# Power.net
KiCad netlist of a schematic drawn in Altium Designer
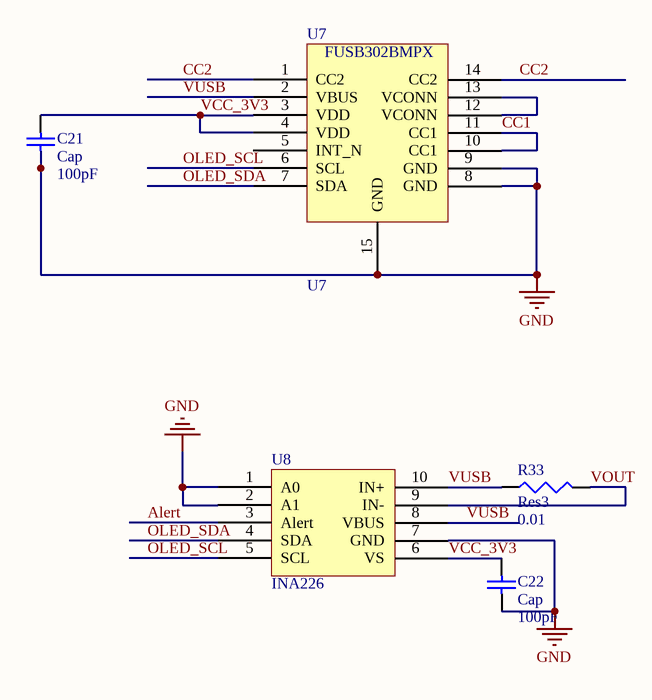
[diagram p0: Power.SchDoc]

(export (version "E")
  (design (tool "Eeschema 10.0.6"))
  (components
    (comp (ref "C21")
      (value "Cap")
      (footprint "0402")
      (description "Capacitor")
      (fields (field (name "ALTIUM_VALUE") "100pF") (field (name "PUBLISHER") "Altium Limited"))
      (libsource (lib "Miscellaneous Devices") (part "Cap"))
    )
    (comp (ref "C22")
      (value "Cap")
      (footprint "0402")
      (description "Capacitor")
      (fields (field (name "ALTIUM_VALUE") "100pF") (field (name "PUBLISHER") "Altium Limited"))
      (libsource (lib "Miscellaneous Devices") (part "Cap"))
    )
    (comp (ref "R33")
      (value "Res3")
      (footprint "C2512")
      (description "Resistor")
      (fields (field (name "ALTIUM_VALUE") "0.01") (field (name "PUBLISHER") "Altium Limited"))
      (libsource (lib "Miscellaneous Devices") (part "Res3"))
    )
    (comp (ref "U7") (value "U7") (footprint "MCL14") (libsource (lib "FUSB302") (part "FUSB302B")))
    (comp (ref "U8") (value "INA226") (footprint "SSOP10") (libsource (lib "INA226") (part "INA226")))
  )
  (nets
    (net (code "1") (name "/Alert") (class "Default")
      (node (ref "U8") (pin "3") (pinfunction "Alert_3") (pintype "passive"))
    )
    (net (code "2") (name "/CC1") (class "Default")
      (node (ref "U7") (pin "10") (pinfunction "CC1_10") (pintype "passive"))
      (node (ref "U7") (pin "11") (pinfunction "CC1_11") (pintype "passive"))
    )
    (net (code "3") (name "/CC2") (class "Default")
      (node (ref "U7") (pin "1") (pinfunction "CC2_1") (pintype "passive"))
      (node (ref "U7") (pin "14") (pinfunction "CC2_14") (pintype "passive"))
    )
    (net (code "4") (name "/OLED_SCL") (class "Default")
      (node (ref "U7") (pin "6") (pinfunction "SCL_6") (pintype "passive"))
      (node (ref "U8") (pin "5") (pinfunction "SCL_5") (pintype "passive"))
    )
    (net (code "5") (name "/OLED_SDA") (class "Default")
      (node (ref "U7") (pin "7") (pinfunction "SDA_7") (pintype "passive"))
      (node (ref "U8") (pin "4") (pinfunction "SDA_4") (pintype "passive"))
    )
    (net (code "6") (name "/VCC_3V3") (class "Default")
      (node (ref "C21") (pin "2") (pinfunction "2_2") (pintype "passive"))
      (node (ref "C22") (pin "2") (pinfunction "2_2") (pintype "passive"))
      (node (ref "U7") (pin "3") (pinfunction "VDD_3") (pintype "passive"))
      (node (ref "U7") (pin "4") (pinfunction "VDD_4") (pintype "passive"))
      (node (ref "U8") (pin "6") (pinfunction "VS_6") (pintype "passive"))
    )
    (net (code "7") (name "/VOUT") (class "Default")
      (node (ref "R33") (pin "2") (pinfunction "2_2") (pintype "passive"))
      (node (ref "U8") (pin "9") (pinfunction "IN-_9") (pintype "passive"))
    )
    (net (code "8") (name "/VUSB") (class "Default")
      (node (ref "R33") (pin "1") (pinfunction "1_1") (pintype "passive"))
      (node (ref "U7") (pin "2") (pinfunction "VBUS_2") (pintype "passive"))
      (node (ref "U8") (pin "10") (pinfunction "IN+_10") (pintype "passive"))
      (node (ref "U8") (pin "8") (pinfunction "VBUS_8") (pintype "passive"))
    )
    (net (code "9") (name "GND") (class "Default")
      (node (ref "C21") (pin "1") (pinfunction "1_1") (pintype "passive"))
      (node (ref "C22") (pin "1") (pinfunction "1_1") (pintype "passive"))
      (node (ref "U7") (pin "15") (pinfunction "GND_15") (pintype "passive"))
      (node (ref "U7") (pin "8") (pinfunction "GND_8") (pintype "passive"))
      (node (ref "U7") (pin "9") (pinfunction "GND_9") (pintype "passive"))
      (node (ref "U8") (pin "1") (pinfunction "A0_1") (pintype "passive"))
      (node (ref "U8") (pin "2") (pinfunction "A1_2") (pintype "passive"))
      (node (ref "U8") (pin "7") (pinfunction "GND_7") (pintype "passive"))
    )
    (net (code "10") (name "Net-(U7-VCONN-Pad12)") (class "Default")
      (node (ref "U7") (pin "12") (pinfunction "VCONN_12") (pintype "passive"))
      (node (ref "U7") (pin "13") (pinfunction "VCONN_13") (pintype "passive"))
    )
    (net (code "11") (name "unconnected-(U7-INT_N-Pad5)") (class "Default")
      (node (ref "U7") (pin "5") (pinfunction "INT_N_5") (pintype "passive"))
    )
  )
)
